# source_selector_v2.net
KiCad netlist of a schematic drawn in EAGLE
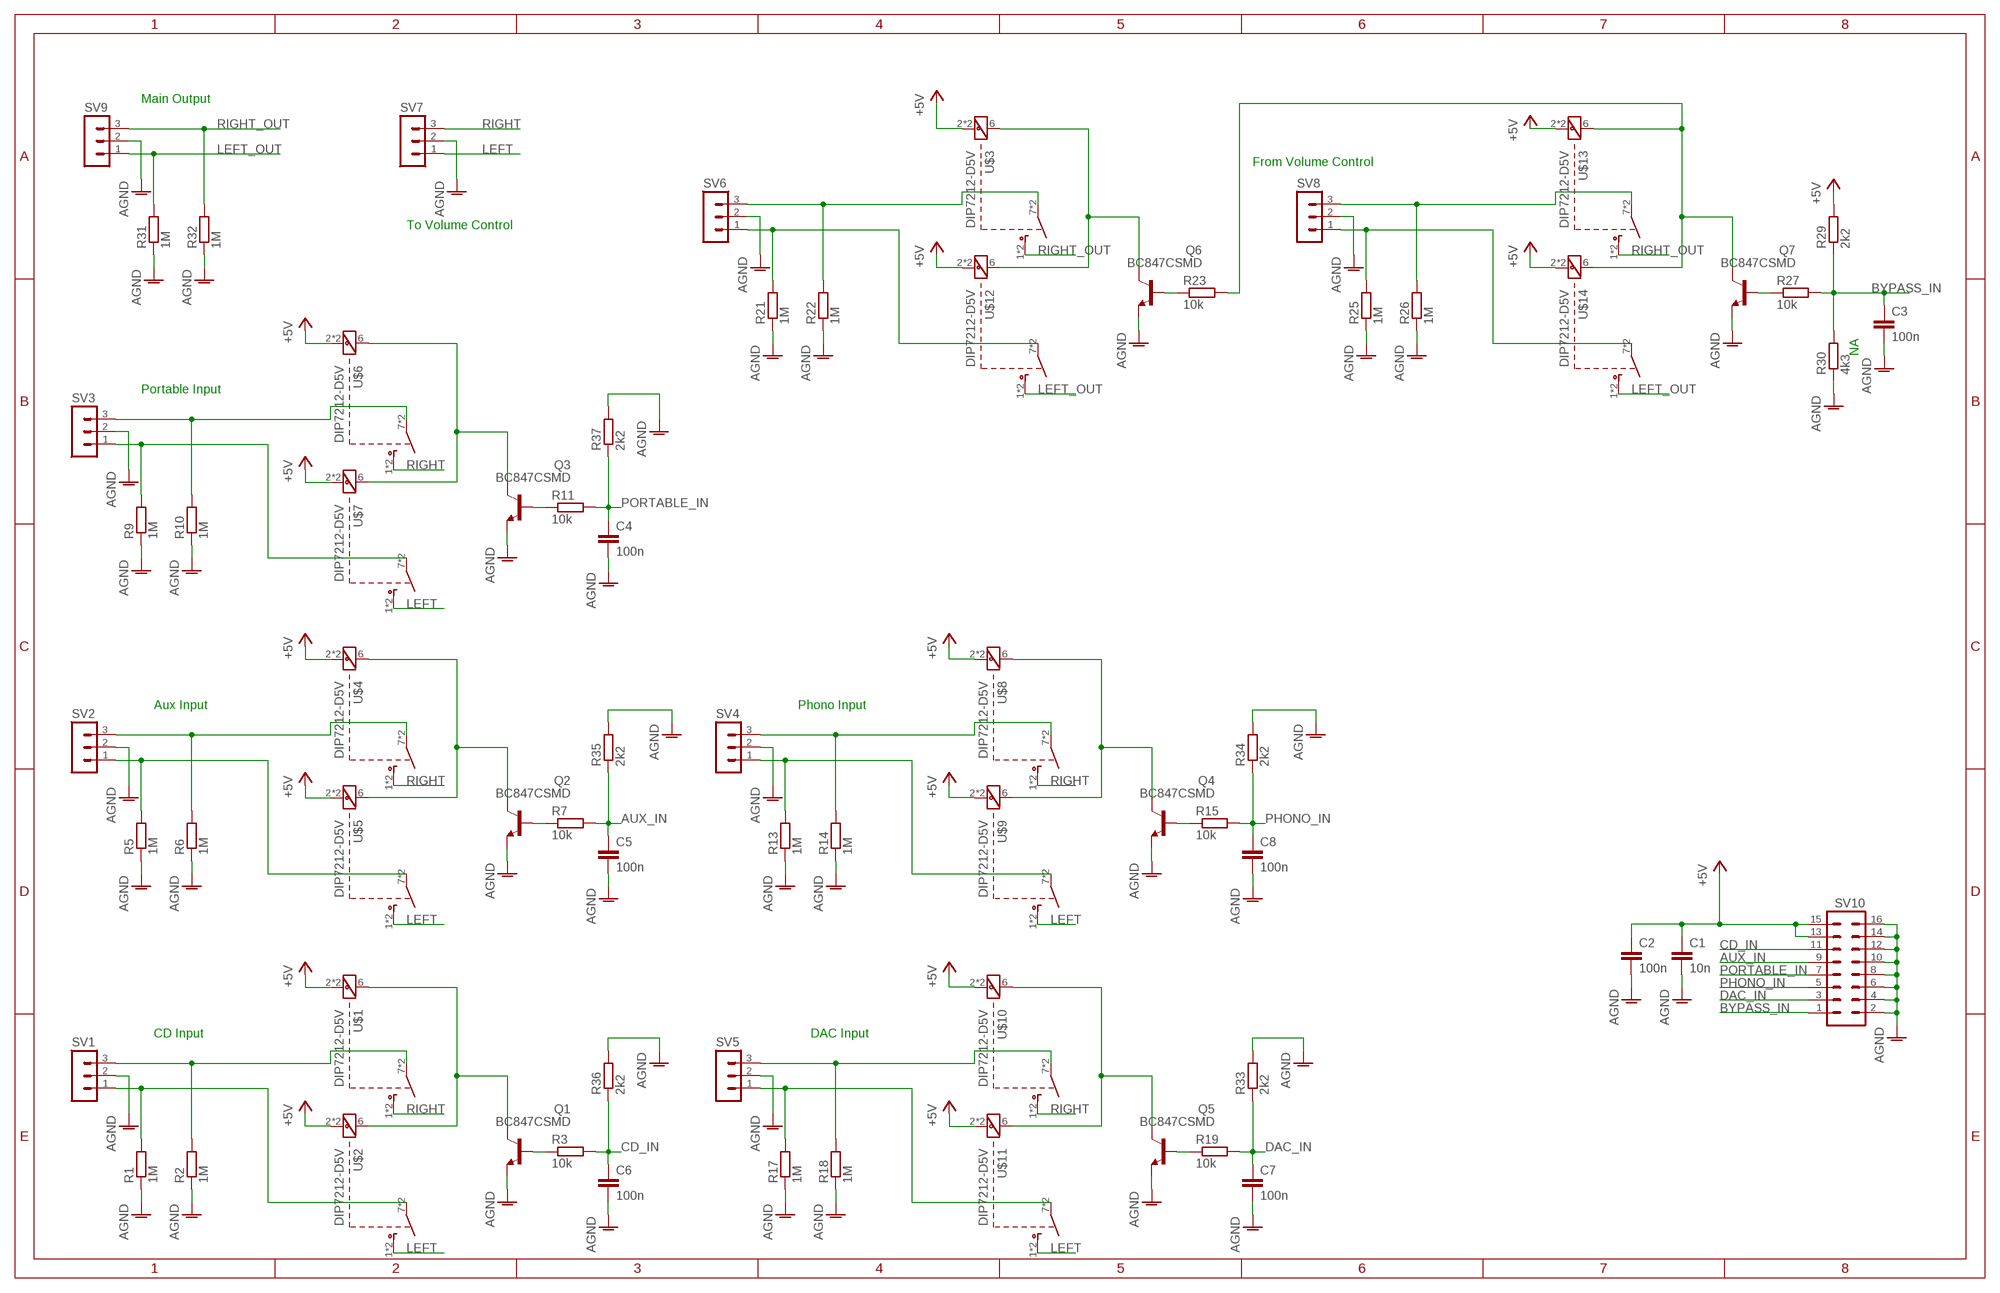
[diagram p0: schematic, sheet 1]

(export (version "E")
  (design (tool "Eeschema 10.0.6"))
  (components
    (comp (ref "C1")
      (value "10n")
      (footprint "eagle-import:C0603")
      (libsource (lib "eagle-import") (part "C-EUC0603"))
    )
    (comp (ref "C2")
      (value "100n")
      (footprint "eagle-import:C0603")
      (libsource (lib "eagle-import") (part "C-EUC0603"))
    )
    (comp (ref "C3")
      (value "100n")
      (footprint "eagle-import:C0603")
      (libsource (lib "eagle-import") (part "C-EUC0603"))
    )
    (comp (ref "C4")
      (value "100n")
      (footprint "eagle-import:C0603")
      (libsource (lib "eagle-import") (part "C-EUC0603"))
    )
    (comp (ref "C5")
      (value "100n")
      (footprint "eagle-import:C0603")
      (libsource (lib "eagle-import") (part "C-EUC0603"))
    )
    (comp (ref "C6")
      (value "100n")
      (footprint "eagle-import:C0603")
      (libsource (lib "eagle-import") (part "C-EUC0603"))
    )
    (comp (ref "C7")
      (value "100n")
      (footprint "eagle-import:C0603")
      (libsource (lib "eagle-import") (part "C-EUC0603"))
    )
    (comp (ref "C8")
      (value "100n")
      (footprint "eagle-import:C0603")
      (libsource (lib "eagle-import") (part "C-EUC0603"))
    )
    (comp (ref "Q1")
      (value "BC847CSMD")
      (footprint "eagle-import:SOT23")
      (libsource (lib "eagle-import") (part "BC847SMDC"))
    )
    (comp (ref "Q2")
      (value "BC847CSMD")
      (footprint "eagle-import:SOT23")
      (libsource (lib "eagle-import") (part "BC847SMDC"))
    )
    (comp (ref "Q3")
      (value "BC847CSMD")
      (footprint "eagle-import:SOT23")
      (libsource (lib "eagle-import") (part "BC847SMDC"))
    )
    (comp (ref "Q4")
      (value "BC847CSMD")
      (footprint "eagle-import:SOT23")
      (libsource (lib "eagle-import") (part "BC847SMDC"))
    )
    (comp (ref "Q5")
      (value "BC847CSMD")
      (footprint "eagle-import:SOT23")
      (libsource (lib "eagle-import") (part "BC847SMDC"))
    )
    (comp (ref "Q6")
      (value "BC847CSMD")
      (footprint "eagle-import:SOT23")
      (libsource (lib "eagle-import") (part "BC847SMDC"))
    )
    (comp (ref "Q7")
      (value "BC847CSMD")
      (footprint "eagle-import:SOT23")
      (libsource (lib "eagle-import") (part "BC847SMDC"))
    )
    (comp (ref "R1")
      (value "1M")
      (footprint "eagle-import:R0603")
      (libsource (lib "eagle-import") (part "R-EU_R0603"))
    )
    (comp (ref "R2")
      (value "1M")
      (footprint "eagle-import:R0603")
      (libsource (lib "eagle-import") (part "R-EU_R0603"))
    )
    (comp (ref "R3")
      (value "10k")
      (footprint "eagle-import:R0603")
      (libsource (lib "eagle-import") (part "R-EU_R0603"))
    )
    (comp (ref "R5")
      (value "1M")
      (footprint "eagle-import:R0603")
      (libsource (lib "eagle-import") (part "R-EU_R0603"))
    )
    (comp (ref "R6")
      (value "1M")
      (footprint "eagle-import:R0603")
      (libsource (lib "eagle-import") (part "R-EU_R0603"))
    )
    (comp (ref "R7")
      (value "10k")
      (footprint "eagle-import:R0603")
      (libsource (lib "eagle-import") (part "R-EU_R0603"))
    )
    (comp (ref "R9")
      (value "1M")
      (footprint "eagle-import:R0603")
      (libsource (lib "eagle-import") (part "R-EU_R0603"))
    )
    (comp (ref "R10")
      (value "1M")
      (footprint "eagle-import:R0603")
      (libsource (lib "eagle-import") (part "R-EU_R0603"))
    )
    (comp (ref "R11")
      (value "10k")
      (footprint "eagle-import:R0603")
      (libsource (lib "eagle-import") (part "R-EU_R0603"))
    )
    (comp (ref "R13")
      (value "1M")
      (footprint "eagle-import:R0603")
      (libsource (lib "eagle-import") (part "R-EU_R0603"))
    )
    (comp (ref "R14")
      (value "1M")
      (footprint "eagle-import:R0603")
      (libsource (lib "eagle-import") (part "R-EU_R0603"))
    )
    (comp (ref "R15")
      (value "10k")
      (footprint "eagle-import:R0603")
      (libsource (lib "eagle-import") (part "R-EU_R0603"))
    )
    (comp (ref "R17")
      (value "1M")
      (footprint "eagle-import:R0603")
      (libsource (lib "eagle-import") (part "R-EU_R0603"))
    )
    (comp (ref "R18")
      (value "1M")
      (footprint "eagle-import:R0603")
      (libsource (lib "eagle-import") (part "R-EU_R0603"))
    )
    (comp (ref "R19")
      (value "10k")
      (footprint "eagle-import:R0603")
      (libsource (lib "eagle-import") (part "R-EU_R0603"))
    )
    (comp (ref "R21")
      (value "1M")
      (footprint "eagle-import:R0603")
      (libsource (lib "eagle-import") (part "R-EU_R0603"))
    )
    (comp (ref "R22")
      (value "1M")
      (footprint "eagle-import:R0603")
      (libsource (lib "eagle-import") (part "R-EU_R0603"))
    )
    (comp (ref "R23")
      (value "10k")
      (footprint "eagle-import:R0603")
      (libsource (lib "eagle-import") (part "R-EU_R0603"))
    )
    (comp (ref "R25")
      (value "1M")
      (footprint "eagle-import:R0603")
      (libsource (lib "eagle-import") (part "R-EU_R0603"))
    )
    (comp (ref "R26")
      (value "1M")
      (footprint "eagle-import:R0603")
      (libsource (lib "eagle-import") (part "R-EU_R0603"))
    )
    (comp (ref "R27")
      (value "10k")
      (footprint "eagle-import:R0603")
      (libsource (lib "eagle-import") (part "R-EU_R0603"))
    )
    (comp (ref "R29")
      (value "2k2")
      (footprint "eagle-import:R0603")
      (libsource (lib "eagle-import") (part "R-EU_R0603"))
    )
    (comp (ref "R30")
      (value "4k3")
      (footprint "eagle-import:R0603")
      (libsource (lib "eagle-import") (part "R-EU_R0603"))
    )
    (comp (ref "R31")
      (value "1M")
      (footprint "eagle-import:R0603")
      (libsource (lib "eagle-import") (part "R-EU_R0603"))
    )
    (comp (ref "R32")
      (value "1M")
      (footprint "eagle-import:R0603")
      (libsource (lib "eagle-import") (part "R-EU_R0603"))
    )
    (comp (ref "R33")
      (value "2k2")
      (footprint "eagle-import:R0603")
      (libsource (lib "eagle-import") (part "R-EU_R0603"))
    )
    (comp (ref "R34")
      (value "2k2")
      (footprint "eagle-import:R0603")
      (libsource (lib "eagle-import") (part "R-EU_R0603"))
    )
    (comp (ref "R35")
      (value "2k2")
      (footprint "eagle-import:R0603")
      (libsource (lib "eagle-import") (part "R-EU_R0603"))
    )
    (comp (ref "R36")
      (value "2k2")
      (footprint "eagle-import:R0603")
      (libsource (lib "eagle-import") (part "R-EU_R0603"))
    )
    (comp (ref "R37")
      (value "2k2")
      (footprint "eagle-import:R0603")
      (libsource (lib "eagle-import") (part "R-EU_R0603"))
    )
    (comp (ref "SV1")
      (value "MA03-1")
      (footprint "eagle-import:MA03-1")
      (libsource (lib "eagle-import") (part "MA03-1"))
    )
    (comp (ref "SV2")
      (value "MA03-1")
      (footprint "eagle-import:MA03-1")
      (libsource (lib "eagle-import") (part "MA03-1"))
    )
    (comp (ref "SV3")
      (value "MA03-1")
      (footprint "eagle-import:MA03-1")
      (libsource (lib "eagle-import") (part "MA03-1"))
    )
    (comp (ref "SV4")
      (value "MA03-1")
      (footprint "eagle-import:MA03-1")
      (libsource (lib "eagle-import") (part "MA03-1"))
    )
    (comp (ref "SV5")
      (value "MA03-1")
      (footprint "eagle-import:MA03-1")
      (libsource (lib "eagle-import") (part "MA03-1"))
    )
    (comp (ref "SV6")
      (value "MA03-1")
      (footprint "eagle-import:MA03-1")
      (libsource (lib "eagle-import") (part "MA03-1"))
    )
    (comp (ref "SV7")
      (value "MA03-1")
      (footprint "eagle-import:MA03-1")
      (libsource (lib "eagle-import") (part "MA03-1"))
    )
    (comp (ref "SV8")
      (value "MA03-1")
      (footprint "eagle-import:MA03-1")
      (libsource (lib "eagle-import") (part "MA03-1"))
    )
    (comp (ref "SV9")
      (value "MA03-1")
      (footprint "eagle-import:MA03-1")
      (libsource (lib "eagle-import") (part "MA03-1"))
    )
    (comp (ref "SV10")
      (value "MA08-2")
      (footprint "eagle-import:MA08-2")
      (libsource (lib "eagle-import") (part "MA08-2"))
    )
    (comp (ref "U$1")
      (value "DIP7212-D5V")
      (footprint "eagle-import:DP-07")
      (libsource (lib "eagle-import") (part "DIP7212-D5V"))
    )
    (comp (ref "U$2")
      (value "DIP7212-D5V")
      (footprint "eagle-import:DP-07")
      (libsource (lib "eagle-import") (part "DIP7212-D5V"))
    )
    (comp (ref "U$3")
      (value "DIP7212-D5V")
      (footprint "eagle-import:DP-07")
      (libsource (lib "eagle-import") (part "DIP7212-D5V"))
    )
    (comp (ref "U$4")
      (value "DIP7212-D5V")
      (footprint "eagle-import:DP-07")
      (libsource (lib "eagle-import") (part "DIP7212-D5V"))
    )
    (comp (ref "U$5")
      (value "DIP7212-D5V")
      (footprint "eagle-import:DP-07")
      (libsource (lib "eagle-import") (part "DIP7212-D5V"))
    )
    (comp (ref "U$6")
      (value "DIP7212-D5V")
      (footprint "eagle-import:DP-07")
      (libsource (lib "eagle-import") (part "DIP7212-D5V"))
    )
    (comp (ref "U$7")
      (value "DIP7212-D5V")
      (footprint "eagle-import:DP-07")
      (libsource (lib "eagle-import") (part "DIP7212-D5V"))
    )
    (comp (ref "U$8")
      (value "DIP7212-D5V")
      (footprint "eagle-import:DP-07")
      (libsource (lib "eagle-import") (part "DIP7212-D5V"))
    )
    (comp (ref "U$9")
      (value "DIP7212-D5V")
      (footprint "eagle-import:DP-07")
      (libsource (lib "eagle-import") (part "DIP7212-D5V"))
    )
    (comp (ref "U$10")
      (value "DIP7212-D5V")
      (footprint "eagle-import:DP-07")
      (libsource (lib "eagle-import") (part "DIP7212-D5V"))
    )
    (comp (ref "U$11")
      (value "DIP7212-D5V")
      (footprint "eagle-import:DP-07")
      (libsource (lib "eagle-import") (part "DIP7212-D5V"))
    )
    (comp (ref "U$12")
      (value "DIP7212-D5V")
      (footprint "eagle-import:DP-07")
      (libsource (lib "eagle-import") (part "DIP7212-D5V"))
    )
    (comp (ref "U$13")
      (value "DIP7212-D5V")
      (footprint "eagle-import:DP-07")
      (libsource (lib "eagle-import") (part "DIP7212-D5V"))
    )
    (comp (ref "U$14")
      (value "DIP7212-D5V")
      (footprint "eagle-import:DP-07")
      (libsource (lib "eagle-import") (part "DIP7212-D5V"))
    )
  )
  (nets
    (net (code "1") (name "+5V") (class "Default")
      (node (ref "C1") (pin "1") (pinfunction "1_1") (pintype "passive"))
      (node (ref "C2") (pin "1") (pinfunction "1_1") (pintype "passive"))
      (node (ref "R29") (pin "2") (pinfunction "2_2") (pintype "passive"))
      (node (ref "SV10") (pin "13") (pinfunction "13_13") (pintype "passive"))
      (node (ref "SV10") (pin "15") (pinfunction "15_15") (pintype "passive"))
      (node (ref "U$1") (pin "13") (pinfunction "1_13") (pintype "passive"))
      (node (ref "U$1") (pin "2") (pinfunction "1_2") (pintype "passive"))
      (node (ref "U$10") (pin "13") (pinfunction "1_13") (pintype "passive"))
      (node (ref "U$10") (pin "2") (pinfunction "1_2") (pintype "passive"))
      (node (ref "U$11") (pin "13") (pinfunction "1_13") (pintype "passive"))
      (node (ref "U$11") (pin "2") (pinfunction "1_2") (pintype "passive"))
      (node (ref "U$12") (pin "13") (pinfunction "1_13") (pintype "passive"))
      (node (ref "U$12") (pin "2") (pinfunction "1_2") (pintype "passive"))
      (node (ref "U$13") (pin "13") (pinfunction "1_13") (pintype "passive"))
      (node (ref "U$13") (pin "2") (pinfunction "1_2") (pintype "passive"))
      (node (ref "U$14") (pin "13") (pinfunction "1_13") (pintype "passive"))
      (node (ref "U$14") (pin "2") (pinfunction "1_2") (pintype "passive"))
      (node (ref "U$2") (pin "13") (pinfunction "1_13") (pintype "passive"))
      (node (ref "U$2") (pin "2") (pinfunction "1_2") (pintype "passive"))
      (node (ref "U$3") (pin "13") (pinfunction "1_13") (pintype "passive"))
      (node (ref "U$3") (pin "2") (pinfunction "1_2") (pintype "passive"))
      (node (ref "U$4") (pin "13") (pinfunction "1_13") (pintype "passive"))
      (node (ref "U$4") (pin "2") (pinfunction "1_2") (pintype "passive"))
      (node (ref "U$5") (pin "13") (pinfunction "1_13") (pintype "passive"))
      (node (ref "U$5") (pin "2") (pinfunction "1_2") (pintype "passive"))
      (node (ref "U$6") (pin "13") (pinfunction "1_13") (pintype "passive"))
      (node (ref "U$6") (pin "2") (pinfunction "1_2") (pintype "passive"))
      (node (ref "U$7") (pin "13") (pinfunction "1_13") (pintype "passive"))
      (node (ref "U$7") (pin "2") (pinfunction "1_2") (pintype "passive"))
      (node (ref "U$8") (pin "13") (pinfunction "1_13") (pintype "passive"))
      (node (ref "U$8") (pin "2") (pinfunction "1_2") (pintype "passive"))
      (node (ref "U$9") (pin "13") (pinfunction "1_13") (pintype "passive"))
      (node (ref "U$9") (pin "2") (pinfunction "1_2") (pintype "passive"))
    )
    (net (code "2") (name "/AUX_IN") (class "Default")
      (node (ref "C5") (pin "1") (pinfunction "1_1") (pintype "passive"))
      (node (ref "R35") (pin "1") (pinfunction "1_1") (pintype "passive"))
      (node (ref "R7") (pin "2") (pinfunction "2_2") (pintype "passive"))
      (node (ref "SV10") (pin "9") (pinfunction "9_9") (pintype "passive"))
    )
    (net (code "3") (name "/BYPASS_IN") (class "Default")
      (node (ref "C3") (pin "1") (pinfunction "1_1") (pintype "passive"))
      (node (ref "R27") (pin "2") (pinfunction "2_2") (pintype "passive"))
      (node (ref "R29") (pin "1") (pinfunction "1_1") (pintype "passive"))
      (node (ref "R30") (pin "2") (pinfunction "2_2") (pintype "passive"))
      (node (ref "SV10") (pin "1") (pinfunction "1_1") (pintype "passive"))
    )
    (net (code "4") (name "/CD_IN") (class "Default")
      (node (ref "C6") (pin "1") (pinfunction "1_1") (pintype "passive"))
      (node (ref "R3") (pin "2") (pinfunction "2_2") (pintype "passive"))
      (node (ref "R36") (pin "1") (pinfunction "1_1") (pintype "passive"))
      (node (ref "SV10") (pin "11") (pinfunction "11_11") (pintype "passive"))
    )
    (net (code "5") (name "/DAC_IN") (class "Default")
      (node (ref "C7") (pin "1") (pinfunction "1_1") (pintype "passive"))
      (node (ref "R19") (pin "2") (pinfunction "2_2") (pintype "passive"))
      (node (ref "R33") (pin "1") (pinfunction "1_1") (pintype "passive"))
      (node (ref "SV10") (pin "3") (pinfunction "3_3") (pintype "passive"))
    )
    (net (code "6") (name "/LEFT") (class "Default")
      (node (ref "SV7") (pin "1") (pinfunction "1_1") (pintype "passive"))
      (node (ref "U$11") (pin "1") (pinfunction "6_1") (pintype "passive"))
      (node (ref "U$11") (pin "14") (pinfunction "6_14") (pintype "passive"))
      (node (ref "U$2") (pin "1") (pinfunction "6_1") (pintype "passive"))
      (node (ref "U$2") (pin "14") (pinfunction "6_14") (pintype "passive"))
      (node (ref "U$5") (pin "1") (pinfunction "6_1") (pintype "passive"))
      (node (ref "U$5") (pin "14") (pinfunction "6_14") (pintype "passive"))
      (node (ref "U$7") (pin "1") (pinfunction "6_1") (pintype "passive"))
      (node (ref "U$7") (pin "14") (pinfunction "6_14") (pintype "passive"))
      (node (ref "U$9") (pin "1") (pinfunction "6_1") (pintype "passive"))
      (node (ref "U$9") (pin "14") (pinfunction "6_14") (pintype "passive"))
    )
    (net (code "7") (name "/LEFT_OUT") (class "Default")
      (node (ref "R31") (pin "2") (pinfunction "2_2") (pintype "passive"))
      (node (ref "SV9") (pin "1") (pinfunction "1_1") (pintype "passive"))
      (node (ref "U$12") (pin "1") (pinfunction "6_1") (pintype "passive"))
      (node (ref "U$12") (pin "14") (pinfunction "6_14") (pintype "passive"))
      (node (ref "U$14") (pin "1") (pinfunction "6_1") (pintype "passive"))
      (node (ref "U$14") (pin "14") (pinfunction "6_14") (pintype "passive"))
    )
    (net (code "8") (name "/PHONO_IN") (class "Default")
      (node (ref "C8") (pin "1") (pinfunction "1_1") (pintype "passive"))
      (node (ref "R15") (pin "2") (pinfunction "2_2") (pintype "passive"))
      (node (ref "R34") (pin "1") (pinfunction "1_1") (pintype "passive"))
      (node (ref "SV10") (pin "5") (pinfunction "5_5") (pintype "passive"))
    )
    (net (code "9") (name "/PORTABLE_IN") (class "Default")
      (node (ref "C4") (pin "1") (pinfunction "1_1") (pintype "passive"))
      (node (ref "R11") (pin "2") (pinfunction "2_2") (pintype "passive"))
      (node (ref "R37") (pin "1") (pinfunction "1_1") (pintype "passive"))
      (node (ref "SV10") (pin "7") (pinfunction "7_7") (pintype "passive"))
    )
    (net (code "10") (name "/RIGHT") (class "Default")
      (node (ref "SV7") (pin "3") (pinfunction "3_3") (pintype "passive"))
      (node (ref "U$1") (pin "1") (pinfunction "6_1") (pintype "passive"))
      (node (ref "U$1") (pin "14") (pinfunction "6_14") (pintype "passive"))
      (node (ref "U$10") (pin "1") (pinfunction "6_1") (pintype "passive"))
      (node (ref "U$10") (pin "14") (pinfunction "6_14") (pintype "passive"))
      (node (ref "U$4") (pin "1") (pinfunction "6_1") (pintype "passive"))
      (node (ref "U$4") (pin "14") (pinfunction "6_14") (pintype "passive"))
      (node (ref "U$6") (pin "1") (pinfunction "6_1") (pintype "passive"))
      (node (ref "U$6") (pin "14") (pinfunction "6_14") (pintype "passive"))
      (node (ref "U$8") (pin "1") (pinfunction "6_1") (pintype "passive"))
      (node (ref "U$8") (pin "14") (pinfunction "6_14") (pintype "passive"))
    )
    (net (code "11") (name "/RIGHT_OUT") (class "Default")
      (node (ref "R32") (pin "2") (pinfunction "2_2") (pintype "passive"))
      (node (ref "SV9") (pin "3") (pinfunction "3_3") (pintype "passive"))
      (node (ref "U$13") (pin "1") (pinfunction "6_1") (pintype "passive"))
      (node (ref "U$13") (pin "14") (pinfunction "6_14") (pintype "passive"))
      (node (ref "U$3") (pin "1") (pinfunction "6_1") (pintype "passive"))
      (node (ref "U$3") (pin "14") (pinfunction "6_14") (pintype "passive"))
    )
    (net (code "12") (name "AGND") (class "Default")
      (node (ref "C1") (pin "2") (pinfunction "2_2") (pintype "passive"))
      (node (ref "C2") (pin "2") (pinfunction "2_2") (pintype "passive"))
      (node (ref "C3") (pin "2") (pinfunction "2_2") (pintype "passive"))
      (node (ref "C4") (pin "2") (pinfunction "2_2") (pintype "passive"))
      (node (ref "C5") (pin "2") (pinfunction "2_2") (pintype "passive"))
      (node (ref "C6") (pin "2") (pinfunction "2_2") (pintype "passive"))
      (node (ref "C7") (pin "2") (pinfunction "2_2") (pintype "passive"))
      (node (ref "C8") (pin "2") (pinfunction "2_2") (pintype "passive"))
      (node (ref "Q1") (pin "2") (pinfunction "E_2") (pintype "passive"))
      (node (ref "Q2") (pin "2") (pinfunction "E_2") (pintype "passive"))
      (node (ref "Q3") (pin "2") (pinfunction "E_2") (pintype "passive"))
      (node (ref "Q4") (pin "2") (pinfunction "E_2") (pintype "passive"))
      (node (ref "Q5") (pin "2") (pinfunction "E_2") (pintype "passive"))
      (node (ref "Q6") (pin "2") (pinfunction "E_2") (pintype "passive"))
      (node (ref "Q7") (pin "2") (pinfunction "E_2") (pintype "passive"))
      (node (ref "R1") (pin "1") (pinfunction "1_1") (pintype "passive"))
      (node (ref "R10") (pin "1") (pinfunction "1_1") (pintype "passive"))
      (node (ref "R13") (pin "1") (pinfunction "1_1") (pintype "passive"))
      (node (ref "R14") (pin "1") (pinfunction "1_1") (pintype "passive"))
      (node (ref "R17") (pin "1") (pinfunction "1_1") (pintype "passive"))
      (node (ref "R18") (pin "1") (pinfunction "1_1") (pintype "passive"))
      (node (ref "R2") (pin "1") (pinfunction "1_1") (pintype "passive"))
      (node (ref "R21") (pin "1") (pinfunction "1_1") (pintype "passive"))
      (node (ref "R22") (pin "1") (pinfunction "1_1") (pintype "passive"))
      (node (ref "R25") (pin "1") (pinfunction "1_1") (pintype "passive"))
      (node (ref "R26") (pin "1") (pinfunction "1_1") (pintype "passive"))
      (node (ref "R30") (pin "1") (pinfunction "1_1") (pintype "passive"))
      (node (ref "R31") (pin "1") (pinfunction "1_1") (pintype "passive"))
      (node (ref "R32") (pin "1") (pinfunction "1_1") (pintype "passive"))
      (node (ref "R33") (pin "2") (pinfunction "2_2") (pintype "passive"))
      (node (ref "R34") (pin "2") (pinfunction "2_2") (pintype "passive"))
      (node (ref "R35") (pin "2") (pinfunction "2_2") (pintype "passive"))
      (node (ref "R36") (pin "2") (pinfunction "2_2") (pintype "passive"))
      (node (ref "R37") (pin "2") (pinfunction "2_2") (pintype "passive"))
      (node (ref "R5") (pin "1") (pinfunction "1_1") (pintype "passive"))
      (node (ref "R6") (pin "1") (pinfunction "1_1") (pintype "passive"))
      (node (ref "R9") (pin "1") (pinfunction "1_1") (pintype "passive"))
      (node (ref "SV1") (pin "2") (pinfunction "2_2") (pintype "passive"))
      (node (ref "SV10") (pin "10") (pinfunction "10_10") (pintype "passive"))
      (node (ref "SV10") (pin "12") (pinfunction "12_12") (pintype "passive"))
      (node (ref "SV10") (pin "14") (pinfunction "14_14") (pintype "passive"))
      (node (ref "SV10") (pin "16") (pinfunction "16_16") (pintype "passive"))
      (node (ref "SV10") (pin "2") (pinfunction "2_2") (pintype "passive"))
      (node (ref "SV10") (pin "4") (pinfunction "4_4") (pintype "passive"))
      (node (ref "SV10") (pin "6") (pinfunction "6_6") (pintype "passive"))
      (node (ref "SV10") (pin "8") (pinfunction "8_8") (pintype "passive"))
      (node (ref "SV2") (pin "2") (pinfunction "2_2") (pintype "passive"))
      (node (ref "SV3") (pin "2") (pinfunction "2_2") (pintype "passive"))
      (node (ref "SV4") (pin "2") (pinfunction "2_2") (pintype "passive"))
      (node (ref "SV5") (pin "2") (pinfunction "2_2") (pintype "passive"))
      (node (ref "SV6") (pin "2") (pinfunction "2_2") (pintype "passive"))
      (node (ref "SV7") (pin "2") (pinfunction "2_2") (pintype "passive"))
      (node (ref "SV8") (pin "2") (pinfunction "2_2") (pintype "passive"))
      (node (ref "SV9") (pin "2") (pinfunction "2_2") (pintype "passive"))
    )
    (net (code "13") (name "Net-(Q1-B)") (class "Default")
      (node (ref "Q1") (pin "1") (pinfunction "B_1") (pintype "passive"))
      (node (ref "R3") (pin "1") (pinfunction "1_1") (pintype "passive"))
    )
    (net (code "14") (name "Net-(Q1-C)") (class "Default")
      (node (ref "Q1") (pin "3") (pinfunction "C_3") (pintype "passive"))
      (node (ref "U$1") (pin "6") (pinfunction "2_6") (pintype "passive"))
      (node (ref "U$2") (pin "6") (pinfunction "2_6") (pintype "passive"))
    )
    (net (code "15") (name "Net-(Q2-B)") (class "Default")
      (node (ref "Q2") (pin "1") (pinfunction "B_1") (pintype "passive"))
      (node (ref "R7") (pin "1") (pinfunction "1_1") (pintype "passive"))
    )
    (net (code "16") (name "Net-(Q2-C)") (class "Default")
      (node (ref "Q2") (pin "3") (pinfunction "C_3") (pintype "passive"))
      (node (ref "U$4") (pin "6") (pinfunction "2_6") (pintype "passive"))
      (node (ref "U$5") (pin "6") (pinfunction "2_6") (pintype "passive"))
    )
    (net (code "17") (name "Net-(Q3-B)") (class "Default")
      (node (ref "Q3") (pin "1") (pinfunction "B_1") (pintype "passive"))
      (node (ref "R11") (pin "1") (pinfunction "1_1") (pintype "passive"))
    )
    (net (code "18") (name "Net-(Q3-C)") (class "Default")
      (node (ref "Q3") (pin "3") (pinfunction "C_3") (pintype "passive"))
      (node (ref "U$6") (pin "6") (pinfunction "2_6") (pintype "passive"))
      (node (ref "U$7") (pin "6") (pinfunction "2_6") (pintype "passive"))
    )
    (net (code "19") (name "Net-(Q4-B)") (class "Default")
      (node (ref "Q4") (pin "1") (pinfunction "B_1") (pintype "passive"))
      (node (ref "R15") (pin "1") (pinfunction "1_1") (pintype "passive"))
    )
    (net (code "20") (name "Net-(Q4-C)") (class "Default")
      (node (ref "Q4") (pin "3") (pinfunction "C_3") (pintype "passive"))
      (node (ref "U$8") (pin "6") (pinfunction "2_6") (pintype "passive"))
      (node (ref "U$9") (pin "6") (pinfunction "2_6") (pintype "passive"))
    )
    (net (code "21") (name "Net-(Q5-B)") (class "Default")
      (node (ref "Q5") (pin "1") (pinfunction "B_1") (pintype "passive"))
      (node (ref "R19") (pin "1") (pinfunction "1_1") (pintype "passive"))
    )
    (net (code "22") (name "Net-(Q5-C)") (class "Default")
      (node (ref "Q5") (pin "3") (pinfunction "C_3") (pintype "passive"))
      (node (ref "U$10") (pin "6") (pinfunction "2_6") (pintype "passive"))
      (node (ref "U$11") (pin "6") (pinfunction "2_6") (pintype "passive"))
    )
    (net (code "23") (name "Net-(Q6-B)") (class "Default")
      (node (ref "Q6") (pin "1") (pinfunction "B_1") (pintype "passive"))
      (node (ref "R23") (pin "1") (pinfunction "1_1") (pintype "passive"))
    )
    (net (code "24") (name "Net-(Q6-C)") (class "Default")
      (node (ref "Q6") (pin "3") (pinfunction "C_3") (pintype "passive"))
      (node (ref "U$12") (pin "6") (pinfunction "2_6") (pintype "passive"))
      (node (ref "U$3") (pin "6") (pinfunction "2_6") (pintype "passive"))
    )
    (net (code "25") (name "Net-(Q7-B)") (class "Default")
      (node (ref "Q7") (pin "1") (pinfunction "B_1") (pintype "passive"))
      (node (ref "R27") (pin "1") (pinfunction "1_1") (pintype "passive"))
    )
    (net (code "26") (name "Net-(Q7-C)") (class "Default")
      (node (ref "Q7") (pin "3") (pinfunction "C_3") (pintype "passive"))
      (node (ref "R23") (pin "2") (pinfunction "2_2") (pintype "passive"))
      (node (ref "U$13") (pin "6") (pinfunction "2_6") (pintype "passive"))
      (node (ref "U$14") (pin "6") (pinfunction "2_6") (pintype "passive"))
    )
    (net (code "27") (name "Net-(R1-Pad2)") (class "Default")
      (node (ref "R1") (pin "2") (pinfunction "2_2") (pintype "passive"))
      (node (ref "SV1") (pin "1") (pinfunction "1_1") (pintype "passive"))
      (node (ref "U$2") (pin "7") (pinfunction "5_7") (pintype "passive"))
      (node (ref "U$2") (pin "8") (pinfunction "5_8") (pintype "passive"))
    )
    (net (code "28") (name "Net-(R2-Pad2)") (class "Default")
      (node (ref "R2") (pin "2") (pinfunction "2_2") (pintype "passive"))
      (node (ref "SV1") (pin "3") (pinfunction "3_3") (pintype "passive"))
      (node (ref "U$1") (pin "7") (pinfunction "5_7") (pintype "passive"))
      (node (ref "U$1") (pin "8") (pinfunction "5_8") (pintype "passive"))
    )
    (net (code "29") (name "Net-(R5-Pad2)") (class "Default")
      (node (ref "R5") (pin "2") (pinfunction "2_2") (pintype "passive"))
      (node (ref "SV2") (pin "1") (pinfunction "1_1") (pintype "passive"))
      (node (ref "U$5") (pin "7") (pinfunction "5_7") (pintype "passive"))
      (node (ref "U$5") (pin "8") (pinfunction "5_8") (pintype "passive"))
    )
    (net (code "30") (name "Net-(R6-Pad2)") (class "Default")
      (node (ref "R6") (pin "2") (pinfunction "2_2") (pintype "passive"))
      (node (ref "SV2") (pin "3") (pinfunction "3_3") (pintype "passive"))
      (node (ref "U$4") (pin "7") (pinfunction "5_7") (pintype "passive"))
      (node (ref "U$4") (pin "8") (pinfunction "5_8") (pintype "passive"))
    )
    (net (code "31") (name "Net-(R9-Pad2)") (class "Default")
      (node (ref "R9") (pin "2") (pinfunction "2_2") (pintype "passive"))
      (node (ref "SV3") (pin "1") (pinfunction "1_1") (pintype "passive"))
      (node (ref "U$7") (pin "7") (pinfunction "5_7") (pintype "passive"))
      (node (ref "U$7") (pin "8") (pinfunction "5_8") (pintype "passive"))
    )
    (net (code "32") (name "Net-(R10-Pad2)") (class "Default")
      (node (ref "R10") (pin "2") (pinfunction "2_2") (pintype "passive"))
      (node (ref "SV3") (pin "3") (pinfunction "3_3") (pintype "passive"))
      (node (ref "U$6") (pin "7") (pinfunction "5_7") (pintype "passive"))
      (node (ref "U$6") (pin "8") (pinfunction "5_8") (pintype "passive"))
    )
    (net (code "33") (name "Net-(R13-Pad2)") (class "Default")
      (node (ref "R13") (pin "2") (pinfunction "2_2") (pintype "passive"))
      (node (ref "SV4") (pin "1") (pinfunction "1_1") (pintype "passive"))
      (node (ref "U$9") (pin "7") (pinfunction "5_7") (pintype "passive"))
      (node (ref "U$9") (pin "8") (pinfunction "5_8") (pintype "passive"))
    )
    (net (code "34") (name "Net-(R14-Pad2)") (class "Default")
      (node (ref "R14") (pin "2") (pinfunction "2_2") (pintype "passive"))
      (node (ref "SV4") (pin "3") (pinfunction "3_3") (pintype "passive"))
      (node (ref "U$8") (pin "7") (pinfunction "5_7") (pintype "passive"))
      (node (ref "U$8") (pin "8") (pinfunction "5_8") (pintype "passive"))
    )
    (net (code "35") (name "Net-(R17-Pad2)") (class "Default")
      (node (ref "R17") (pin "2") (pinfunction "2_2") (pintype "passive"))
      (node (ref "SV5") (pin "1") (pinfunction "1_1") (pintype "passive"))
      (node (ref "U$11") (pin "7") (pinfunction "5_7") (pintype "passive"))
      (node (ref "U$11") (pin "8") (pinfunction "5_8") (pintype "passive"))
    )
    (net (code "36") (name "Net-(R18-Pad2)") (class "Default")
      (node (ref "R18") (pin "2") (pinfunction "2_2") (pintype "passive"))
      (node (ref "SV5") (pin "3") (pinfunction "3_3") (pintype "passive"))
      (node (ref "U$10") (pin "7") (pinfunction "5_7") (pintype "passive"))
      (node (ref "U$10") (pin "8") (pinfunction "5_8") (pintype "passive"))
    )
    (net (code "37") (name "Net-(R21-Pad2)") (class "Default")
      (node (ref "R21") (pin "2") (pinfunction "2_2") (pintype "passive"))
      (node (ref "SV6") (pin "1") (pinfunction "1_1") (pintype "passive"))
      (node (ref "U$12") (pin "7") (pinfunction "5_7") (pintype "passive"))
      (node (ref "U$12") (pin "8") (pinfunction "5_8") (pintype "passive"))
    )
    (net (code "38") (name "Net-(R22-Pad2)") (class "Default")
      (node (ref "R22") (pin "2") (pinfunction "2_2") (pintype "passive"))
      (node (ref "SV6") (pin "3") (pinfunction "3_3") (pintype "passive"))
      (node (ref "U$3") (pin "7") (pinfunction "5_7") (pintype "passive"))
      (node (ref "U$3") (pin "8") (pinfunction "5_8") (pintype "passive"))
    )
    (net (code "39") (name "Net-(R25-Pad2)") (class "Default")
      (node (ref "R25") (pin "2") (pinfunction "2_2") (pintype "passive"))
      (node (ref "SV8") (pin "1") (pinfunction "1_1") (pintype "passive"))
      (node (ref "U$14") (pin "7") (pinfunction "5_7") (pintype "passive"))
      (node (ref "U$14") (pin "8") (pinfunction "5_8") (pintype "passive"))
    )
    (net (code "40") (name "Net-(R26-Pad2)") (class "Default")
      (node (ref "R26") (pin "2") (pinfunction "2_2") (pintype "passive"))
      (node (ref "SV8") (pin "3") (pinfunction "3_3") (pintype "passive"))
      (node (ref "U$13") (pin "7") (pinfunction "5_7") (pintype "passive"))
      (node (ref "U$13") (pin "8") (pinfunction "5_8") (pintype "passive"))
    )
  )
)
